# Test_Board_PCB.net
KiCad netlist of a schematic drawn in Altium Designer
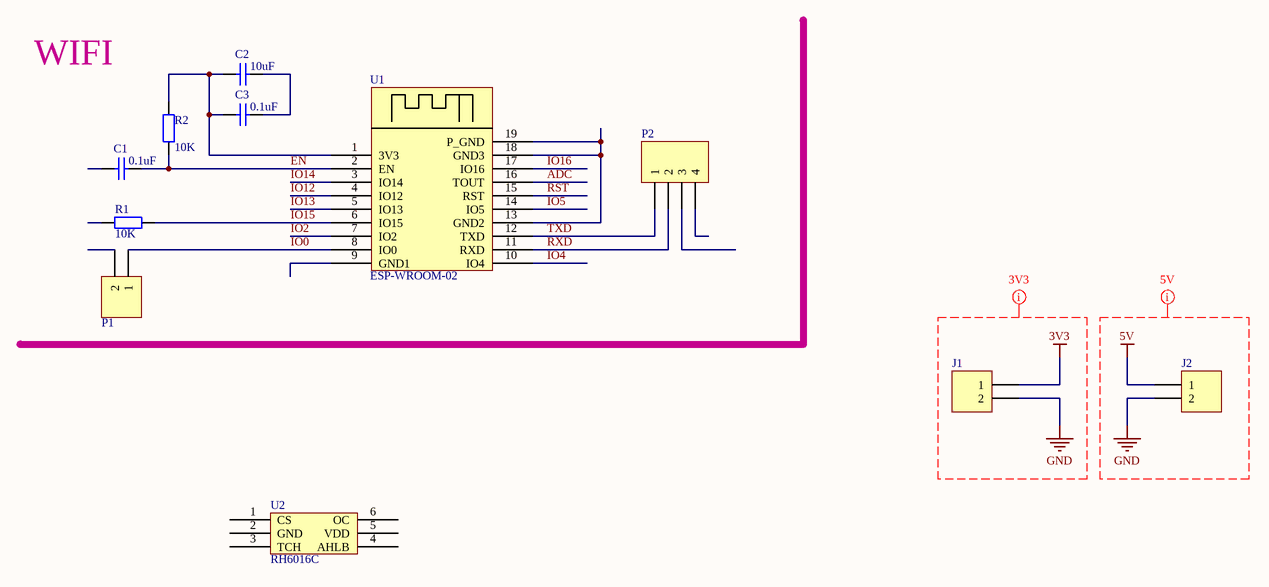
[diagram p0: Test_Board_PCB.SchDoc]

(export (version "E")
  (design (tool "Eeschema 10.0.6"))
  (components
    (comp (ref "C1")
      (value "0.1uF")
      (footprint "C-0603")
      (description "Capacitor")
      (fields (field (name "Comment") "Cap") (field (name "PUBLISHER") "Altium Limited"))
      (libsource (lib "Miscellaneous Devices") (part "Cap"))
    )
    (comp (ref "C2")
      (value "10uF")
      (footprint "C-0805")
      (description "Capacitor")
      (fields (field (name "Comment") "Cap") (field (name "PUBLISHER") "Altium Limited"))
      (libsource (lib "Miscellaneous Devices") (part "Cap"))
    )
    (comp (ref "C3")
      (value "0.1uF")
      (footprint "C-0603")
      (description "Capacitor")
      (fields (field (name "Comment") "Cap") (field (name "PUBLISHER") "Altium Limited"))
      (libsource (lib "Miscellaneous Devices") (part "Cap"))
    )
    (comp (ref "J1")
      (value "Header 2")
      (footprint "HDR1X2")
      (description "Header, 2-Pin")
      (fields (field (name "PUBLISHER") "Altium Limited"))
      (libsource (lib "") (part "Header 2_1"))
    )
    (comp (ref "J2")
      (value "Header 2")
      (footprint "HDR1X2")
      (description "Header, 2-Pin")
      (fields (field (name "PUBLISHER") "Altium Limited"))
      (libsource (lib "Miscellaneous Connectors") (part "Header 2"))
    )
    (comp (ref "P1")
      (value "Header 2")
      (footprint "P1-2,header")
      (description "Header, 2-Pin")
      (fields (field (name "PUBLISHER") "Altium Limited"))
      (libsource (lib "") (part "Header 2_1"))
    )
    (comp (ref "P2")
      (value "Header 4")
      (footprint "P1-4,header")
      (description "Header, 4-Pin")
      (fields (field (name "PUBLISHER") "Altium Limited"))
      (libsource (lib "Miscellaneous Connectors") (part "Header 4"))
    )
    (comp (ref "R1")
      (value "10K")
      (footprint "R-0603")
      (description "Resistor")
      (fields (field (name "Comment") "Res2") (field (name "PUBLISHER") "Altium Limited"))
      (libsource (lib "") (part "Res2_1"))
    )
    (comp (ref "R2")
      (value "10K")
      (footprint "R-0603")
      (description "Resistor")
      (fields (field (name "Comment") "Res2") (field (name "PUBLISHER") "Altium Limited"))
      (libsource (lib "Miscellaneous Devices") (part "Res2"))
    )
    (comp (ref "U1")
      (value "ESP-WROOM-02")
      (footprint "ESP-WROOM-02")
      (libsource (lib "AddMore") (part "ESP-WROOM-02"))
    )
    (comp (ref "U2") (value "RH6016C") (footprint "SOT-23-6") (libsource (lib "AddMore") (part "RH6016C")))
  )
  (nets
    (net (code "1") (name "/ADC") (class "Default")
      (node (ref "U1") (pin "16") (pinfunction "TOUT_16") (pintype "passive"))
    )
    (net (code "2") (name "/EN") (class "Default")
      (node (ref "C1") (pin "2") (pinfunction "2_2") (pintype "passive"))
      (node (ref "R2") (pin "1") (pinfunction "1_1") (pintype "passive"))
      (node (ref "U1") (pin "2") (pinfunction "EN_2") (pintype "passive"))
    )
    (net (code "3") (name "/IO0") (class "Default")
      (node (ref "P1") (pin "1") (pinfunction "1_1") (pintype "passive"))
      (node (ref "U1") (pin "8") (pinfunction "IO0_8") (pintype "passive"))
    )
    (net (code "4") (name "/IO2") (class "Default")
      (node (ref "U1") (pin "7") (pinfunction "IO2_7") (pintype "passive"))
    )
    (net (code "5") (name "/IO4") (class "Default")
      (node (ref "U1") (pin "10") (pinfunction "IO4_10") (pintype "passive"))
    )
    (net (code "6") (name "/IO5") (class "Default")
      (node (ref "U1") (pin "14") (pinfunction "IO5_14") (pintype "passive"))
    )
    (net (code "7") (name "/IO12") (class "Default")
      (node (ref "U1") (pin "4") (pinfunction "IO12_4") (pintype "passive"))
    )
    (net (code "8") (name "/IO13") (class "Default")
      (node (ref "U1") (pin "5") (pinfunction "IO13_5") (pintype "passive"))
    )
    (net (code "9") (name "/IO14") (class "Default")
      (node (ref "U1") (pin "3") (pinfunction "IO14_3") (pintype "passive"))
    )
    (net (code "10") (name "/IO15") (class "Default")
      (node (ref "R1") (pin "1") (pinfunction "1_1") (pintype "passive"))
      (node (ref "U1") (pin "6") (pinfunction "IO15_6") (pintype "passive"))
    )
    (net (code "11") (name "/IO16") (class "Default")
      (node (ref "U1") (pin "17") (pinfunction "IO16_17") (pintype "passive"))
    )
    (net (code "12") (name "/RST") (class "Default")
      (node (ref "U1") (pin "15") (pinfunction "RST_15") (pintype "passive"))
    )
    (net (code "13") (name "/RXD") (class "Default")
      (node (ref "P2") (pin "2") (pinfunction "2_2") (pintype "passive"))
      (node (ref "U1") (pin "11") (pinfunction "RXD_11") (pintype "passive"))
    )
    (net (code "14") (name "/TXD") (class "Default")
      (node (ref "P2") (pin "1") (pinfunction "1_1") (pintype "passive"))
      (node (ref "U1") (pin "12") (pinfunction "TXD_12") (pintype "passive"))
    )
    (net (code "15") (name "3V3") (class "Default")
      (node (ref "J1") (pin "1") (pinfunction "1_1") (pintype "passive"))
    )
    (net (code "16") (name "5V") (class "Default")
      (node (ref "J2") (pin "1") (pinfunction "1_1") (pintype "passive"))
    )
    (net (code "17") (name "GND") (class "Default")
      (node (ref "J1") (pin "2") (pinfunction "2_2") (pintype "passive"))
      (node (ref "J2") (pin "2") (pinfunction "2_2") (pintype "passive"))
    )
    (net (code "18") (name "Net-(C2-Pad2)") (class "Default")
      (node (ref "C2") (pin "2") (pinfunction "2_2") (pintype "passive"))
      (node (ref "C3") (pin "2") (pinfunction "2_2") (pintype "passive"))
    )
    (net (code "19") (name "Net-(U1-3V3)") (class "Default")
      (node (ref "C2") (pin "1") (pinfunction "1_1") (pintype "passive"))
      (node (ref "C3") (pin "1") (pinfunction "1_1") (pintype "passive"))
      (node (ref "R2") (pin "2") (pinfunction "2_2") (pintype "passive"))
      (node (ref "U1") (pin "1") (pinfunction "3V3_1") (pintype "passive"))
    )
    (net (code "20") (name "Net-(U1-GND2)") (class "Default")
      (node (ref "U1") (pin "13") (pinfunction "GND2_13") (pintype "passive"))
      (node (ref "U1") (pin "18") (pinfunction "GND3_18") (pintype "passive"))
      (node (ref "U1") (pin "19") (pinfunction "P_GND_19") (pintype "passive"))
    )
    (net (code "21") (name "unconnected-(C1-Pad1)") (class "Default")
      (node (ref "C1") (pin "1") (pinfunction "1_1") (pintype "passive"))
    )
    (net (code "22") (name "unconnected-(P1-Pad2)") (class "Default")
      (node (ref "P1") (pin "2") (pinfunction "2_2") (pintype "passive"))
    )
    (net (code "23") (name "unconnected-(P2-Pad3)") (class "Default")
      (node (ref "P2") (pin "3") (pinfunction "3_3") (pintype "passive"))
    )
    (net (code "24") (name "unconnected-(P2-Pad4)") (class "Default")
      (node (ref "P2") (pin "4") (pinfunction "4_4") (pintype "passive"))
    )
    (net (code "25") (name "unconnected-(R1-Pad2)") (class "Default")
      (node (ref "R1") (pin "2") (pinfunction "2_2") (pintype "passive"))
    )
    (net (code "26") (name "unconnected-(U1-GND1-Pad9)") (class "Default")
      (node (ref "U1") (pin "9") (pinfunction "GND1_9") (pintype "passive"))
    )
    (net (code "27") (name "unconnected-(U2-AHLB-Pad4)") (class "Default")
      (node (ref "U2") (pin "4") (pinfunction "AHLB_4") (pintype "passive"))
    )
    (net (code "28") (name "unconnected-(U2-CS-Pad1)") (class "Default")
      (node (ref "U2") (pin "1") (pinfunction "CS_1") (pintype "passive"))
    )
    (net (code "29") (name "unconnected-(U2-GND-Pad2)") (class "Default")
      (node (ref "U2") (pin "2") (pinfunction "GND_2") (pintype "passive"))
    )
    (net (code "30") (name "unconnected-(U2-OC-Pad6)") (class "Default")
      (node (ref "U2") (pin "6") (pinfunction "OC_6") (pintype "passive"))
    )
    (net (code "31") (name "unconnected-(U2-TCH-Pad3)") (class "Default")
      (node (ref "U2") (pin "3") (pinfunction "TCH_3") (pintype "passive"))
    )
    (net (code "32") (name "unconnected-(U2-VDD-Pad5)") (class "Default")
      (node (ref "U2") (pin "5") (pinfunction "VDD_5") (pintype "passive"))
    )
  )
)
